# K60_2014_12_12.net
KiCad netlist of a schematic drawn in Altium Designer
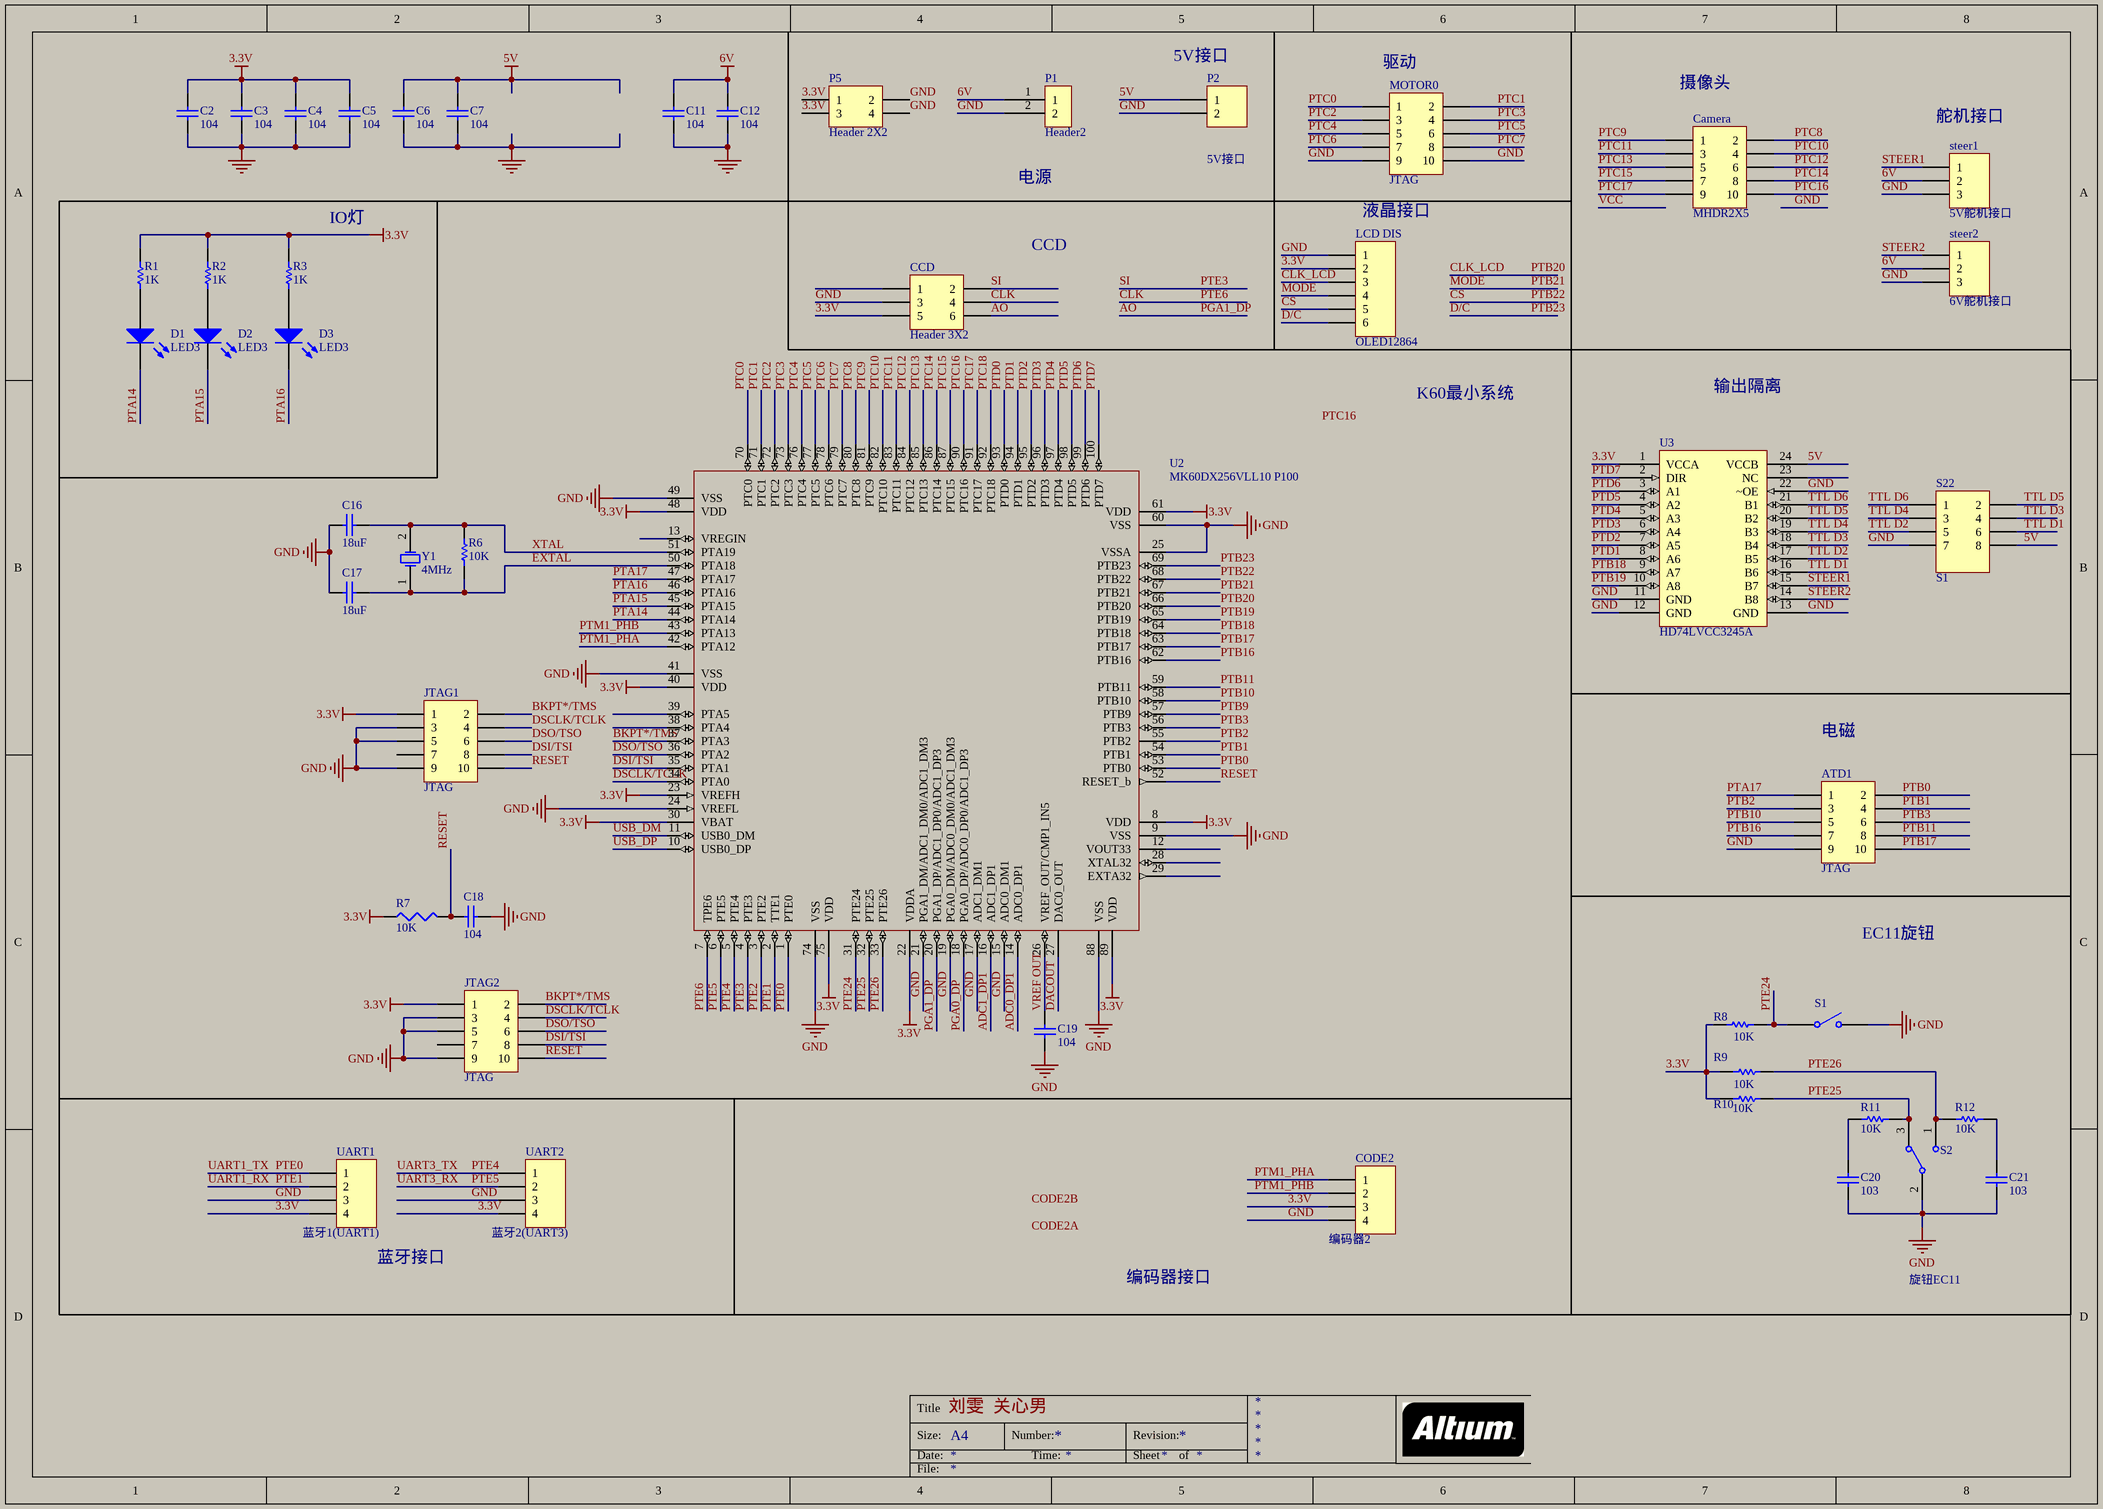
[diagram p0: K60 2014 12 12.SchDoc]

(export (version "E")
  (design (tool "Eeschema 10.0.6"))
  (components
    (comp (ref "ATD1")
      (value "JTAG")
      (footprint "K60 2014 12 12:IDC10S")
      (description "Header, 5-Pin, Dual row")
      (fields (field (name "PUBLISHER") "Altium Limited"))
      (libsource (lib "北京工商大学智能车 K60 摄像头") (part "MHDR2X5"))
    )
    (comp (ref "C2")
      (value "104")
      (footprint "0603")
      (description "Capacitor")
      (libsource (lib "电阻电容") (part "Cap 0603"))
    )
    (comp (ref "C3")
      (value "104")
      (footprint "0603")
      (description "Capacitor")
      (libsource (lib "电阻电容") (part "Cap 0603"))
    )
    (comp (ref "C4")
      (value "104")
      (footprint "0603")
      (description "Capacitor")
      (libsource (lib "电阻电容") (part "Cap 0603"))
    )
    (comp (ref "C5")
      (value "104")
      (footprint "0603")
      (description "Capacitor")
      (libsource (lib "电阻电容") (part "Cap 0603"))
    )
    (comp (ref "C6")
      (value "104")
      (footprint "0603")
      (description "Capacitor")
      (libsource (lib "电阻电容") (part "Cap 0603"))
    )
    (comp (ref "C7")
      (value "104")
      (footprint "0603")
      (description "Capacitor")
      (libsource (lib "电阻电容") (part "Cap 0603"))
    )
    (comp (ref "C11")
      (value "104")
      (footprint "0603")
      (description "Capacitor")
      (libsource (lib "电阻电容") (part "Cap 0603"))
    )
    (comp (ref "C12")
      (value "104")
      (footprint "0603")
      (description "Capacitor")
      (libsource (lib "电阻电容") (part "Cap 0603"))
    )
    (comp (ref "C16")
      (value "18uF")
      (footprint "0603")
      (description "Capacitor")
      (libsource (lib "电阻电容") (part "Cap 0603"))
    )
    (comp (ref "C17")
      (value "18uF")
      (footprint "0603")
      (description "Capacitor")
      (libsource (lib "电阻电容") (part "Cap 0603"))
    )
    (comp (ref "C18")
      (value "104")
      (footprint "0603")
      (description "Capacitor (Semiconductor SIM Model)")
      (fields (field (name "Comment") "C1") (field (name "PUBLISHER") "Altium Limited"))
      (libsource (lib "北京工商大学智能车 K60 摄像头") (part "Cap Semi"))
    )
    (comp (ref "C19")
      (value "104")
      (footprint "0603")
      (description "Capacitor (Semiconductor SIM Model)")
      (fields (field (name "Comment") "C1") (field (name "PUBLISHER") "Altium Limited"))
      (libsource (lib "北京工商大学智能车 K60 摄像头") (part "Cap Semi"))
    )
    (comp (ref "C20")
      (value "103")
      (footprint "0603")
      (description "Capacitor")
      (libsource (lib "电阻电容") (part "Cap 0603"))
    )
    (comp (ref "C21")
      (value "103")
      (footprint "0603")
      (description "Capacitor")
      (libsource (lib "电阻电容") (part "Cap 0603"))
    )
    (comp (ref "Camera")
      (value "MHDR2X5")
      (footprint "IDC10S")
      (description "Header, 5-Pin, Dual row")
      (fields (field (name "PUBLISHER") "Altium Limited"))
      (libsource (lib "Miscellaneous Connectors") (part "MHDR2X5"))
    )
    (comp (ref "CCD")
      (value "Header 3X2")
      (footprint "HDR2X3")
      (description "Header, 3-Pin, Dual row")
      (fields (field (name "PUBLISHER") "Altium Limited"))
      (libsource (lib "Miscellaneous Connectors") (part "Header 3X2"))
    )
    (comp (ref "CODE2")
      (value "编码器2")
      (footprint "HDR1X4")
      (description "Header, 4-Pin")
      (fields (field (name "PUBLISHER") "Altium Limited"))
      (libsource (lib "K60 2014 12 12") (part "Header 4"))
    )
    (comp (ref "D1")
      (value "LED3")
      (footprint "0805")
      (description "Typical BLUE SiC LED")
      (fields (field (name "PUBLISHER") "Altium Limited"))
      (libsource (lib "北京工商大学智能车 K60 摄像头") (part "LED3"))
    )
    (comp (ref "D2")
      (value "LED3")
      (footprint "0805")
      (description "Typical BLUE SiC LED")
      (fields (field (name "PUBLISHER") "Altium Limited"))
      (libsource (lib "北京工商大学智能车 K60 摄像头") (part "LED3"))
    )
    (comp (ref "D3")
      (value "LED3")
      (footprint "0805")
      (description "Typical BLUE SiC LED")
      (fields (field (name "PUBLISHER") "Altium Limited"))
      (libsource (lib "北京工商大学智能车 K60 摄像头") (part "LED3"))
    )
    (comp (ref "JTAG1")
      (value "JTAG")
      (footprint "接口1:JTAG-2.0")
      (description "Header, 5-Pin, Dual row")
      (fields (field (name "PUBLISHER") "Altium Limited"))
      (libsource (lib "北京工商大学智能车 K60 摄像头") (part "MHDR2X5"))
    )
    (comp (ref "JTAG2")
      (value "JTAG")
      (footprint "2014 10 1 主控板 KL25Z128VLK42:MHDR2X5")
      (description "Header, 5-Pin, Dual row")
      (fields (field (name "PUBLISHER") "Altium Limited"))
      (libsource (lib "北京工商大学智能车 K60 摄像头") (part "MHDR2X5"))
    )
    (comp (ref "LCD DIS")
      (value "OLED12864")
      (footprint "HDR1X6")
      (description "Header, 6-Pin")
      (fields (field (name "PUBLISHER") "Altium Limited"))
      (libsource (lib "Miscellaneous Connectors") (part "Header 6"))
    )
    (comp (ref "MOTOR0")
      (value "JTAG")
      (footprint "K60 2014 12 12:IDC10S")
      (description "Header, 5-Pin, Dual row")
      (fields (field (name "PUBLISHER") "Altium Limited"))
      (libsource (lib "北京工商大学智能车 K60 摄像头") (part "MHDR2X5"))
    )
    (comp (ref "P1") (value "Header2") (footprint "DIP2-2.54") (libsource (lib "接口1") (part "Header2")))
    (comp (ref "P2")
      (value "5V接口")
      (footprint "HDR1X2")
      (description "Header, 2-Pin")
      (fields (field (name "PUBLISHER") "Altium Limited"))
      (libsource (lib "Miscellaneous Connectors") (part "Header 2"))
    )
    (comp (ref "P5")
      (value "Header 2X2")
      (footprint "HDR2X2")
      (description "Header, 2-Pin, Dual row")
      (fields (field (name "PUBLISHER") "Altium Limited"))
      (libsource (lib "Miscellaneous Connectors") (part "Header 2X2"))
    )
    (comp (ref "R1")
      (value "1K")
      (footprint "0603")
      (description "Resistor")
      (libsource (lib "电阻电容") (part "Res0603"))
    )
    (comp (ref "R2")
      (value "1K")
      (footprint "0603")
      (description "Resistor")
      (libsource (lib "电阻电容") (part "Res0603"))
    )
    (comp (ref "R3")
      (value "1K")
      (footprint "0603")
      (description "Resistor")
      (libsource (lib "电阻电容") (part "Res0603"))
    )
    (comp (ref "R6")
      (value "10K")
      (footprint "0603")
      (description "Resistor")
      (libsource (lib "电阻电容") (part "Res0603"))
    )
    (comp (ref "R7")
      (value "10K")
      (footprint "0603")
      (description "Resistor")
      (fields (field (name "Comment") "Res3") (field (name "PUBLISHER") "Altium Limited"))
      (libsource (lib "北京工商大学智能车 K60 摄像头") (part "Res3"))
    )
    (comp (ref "R8")
      (value "10K")
      (footprint "0603")
      (description "Resistor")
      (libsource (lib "电阻电容") (part "Res0603"))
    )
    (comp (ref "R9")
      (value "10K")
      (footprint "0603")
      (description "Resistor")
      (libsource (lib "电阻电容") (part "Res0603"))
    )
    (comp (ref "R10")
      (value "10K")
      (footprint "0603")
      (description "Resistor")
      (libsource (lib "电阻电容") (part "Res0603"))
    )
    (comp (ref "R11")
      (value "10K")
      (footprint "0603")
      (description "Resistor")
      (libsource (lib "电阻电容") (part "Res0603"))
    )
    (comp (ref "R12")
      (value "10K")
      (footprint "0603")
      (description "Resistor")
      (libsource (lib "电阻电容") (part "Res0603"))
    )
    (comp (ref "S1")
      (value "~")
      (footprint "BTBU CAR 摄像 K60 2013 4 20:Code_Switch")
      (description "Single-Pole, Single-Throw Switch")
      (fields (field (name "PUBLISHER") "Altium Limited"))
      (libsource (lib "北京工商大学智能车 K60 摄像头") (part "SW-SPST"))
    )
    (comp (ref "S2")
      (value "~")
      (footprint "BTBU CAR 摄像 K60 2013 4 20:Code_Switch")
      (description "SPDT Subminiature Toggle Switch, Right Angle Mounting, Vertical Actuation")
      (fields (field (name "PUBLISHER") "Altium Limited"))
      (libsource (lib "Miscellaneous Devices") (part "SW-SPDT"))
    )
    (comp (ref "S22")
      (value "S1")
      (footprint "K60 2014 12 12:IDC10S")
      (description "Header, 5-Pin, Dual row")
      (fields (field (name "PUBLISHER") "Altium Limited"))
      (libsource (lib "") (part "MHDR2X5_1"))
    )
    (comp (ref "steer1")
      (value "5V舵机接口")
      (footprint "HDR1X3")
      (description "Header, 3-Pin")
      (fields (field (name "PUBLISHER") "Altium Limited"))
      (libsource (lib "Miscellaneous Connectors") (part "Header 3"))
    )
    (comp (ref "steer2")
      (value "6V舵机接口")
      (footprint "HDR1X3")
      (description "Header, 3-Pin")
      (fields (field (name "PUBLISHER") "Altium Limited"))
      (libsource (lib "Miscellaneous Connectors") (part "Header 3"))
    )
    (comp (ref "U2")
      (value "MK60DX256VLL10 P100")
      (footprint "BTBU CAR 摄像 K60 2013 4 20:983-01_M")
      (description "Low Cost Integrated Multiprotocol Processor")
      (fields (field (name "PUBLISHER") "Altium Limited"))
      (libsource (lib "2012 6 10 智能车 摄像头组") (part "MC68LC302PU16"))
    )
    (comp (ref "U3")
      (value "HD74LVCC3245A")
      (footprint "HD74LVCC3245A")
      (description "Octal Bus Transceiver with adjustable output voltage  and 3-state Outputs")
      (libsource (lib "Voltage IC") (part "HD74LVCC3245A"))
    )
    (comp (ref "UART1")
      (value "蓝牙1(UART1)")
      (footprint "HDR1X4")
      (description "Header, 4-Pin")
      (fields (field (name "PUBLISHER") "Altium Limited"))
      (libsource (lib "Miscellaneous Connectors") (part "Header 4"))
    )
    (comp (ref "UART2")
      (value "蓝牙2(UART3)")
      (footprint "HDR1X4")
      (description "Header, 4-Pin")
      (fields (field (name "PUBLISHER") "Altium Limited"))
      (libsource (lib "Miscellaneous Connectors") (part "Header 4"))
    )
    (comp (ref "Y1")
      (value "4MHz")
      (footprint "晶振11.2-4.7-3.6")
      (description "Crystal Oscillator")
      (fields (field (name "PUBLISHER") "Altium Limited"))
      (libsource (lib "北京工商大学智能车 K60 摄像头") (part "XTAL"))
    )
  )
  (nets
    (net (code "1") (name "/ADC0_DP1") (class "Default")
      (node (ref "U2") (pin "14") (pinfunction "ADC0_DP1_14") (pintype "bidirectional"))
    )
    (net (code "2") (name "/ADC1_DP1") (class "Default")
      (node (ref "U2") (pin "16") (pinfunction "ADC1_DP1_16") (pintype "bidirectional"))
    )
    (net (code "3") (name "/AO") (class "Default")
      (node (ref "CCD") (pin "6") (pinfunction "6_6") (pintype "passive"))
      (node (ref "U2") (pin "20") (pinfunction "PGA1_DP/ADC1_DP0/ADC1_DP3_20") (pintype "bidirectional"))
    )
    (net (code "4") (name "/BKPT*{slash}TMS") (class "Default")
      (node (ref "JTAG1") (pin "2") (pinfunction "2_2") (pintype "passive"))
      (node (ref "JTAG2") (pin "2") (pinfunction "2_2") (pintype "passive"))
      (node (ref "U2") (pin "37") (pinfunction "PTA3_37") (pintype "bidirectional"))
    )
    (net (code "5") (name "/CLK") (class "Default")
      (node (ref "CCD") (pin "4") (pinfunction "4_4") (pintype "passive"))
      (node (ref "U2") (pin "7") (pinfunction "TPE6_7") (pintype "bidirectional"))
    )
    (net (code "6") (name "/CLK_LCD") (class "Default")
      (node (ref "LCD DIS") (pin "3") (pinfunction "3_3") (pintype "passive"))
      (node (ref "U2") (pin "66") (pinfunction "PTB20_66") (pintype "bidirectional"))
    )
    (net (code "9") (name "/CS") (class "Default")
      (node (ref "LCD DIS") (pin "5") (pinfunction "5_5") (pintype "passive"))
      (node (ref "U2") (pin "68") (pinfunction "PTB22_68") (pintype "bidirectional"))
    )
    (net (code "10") (name "/DACOUT") (class "Default")
      (node (ref "U2") (pin "27") (pinfunction "DAC0_OUT_27") (pintype "passive"))
    )
    (net (code "11") (name "/DSCLK{slash}TCLK") (class "Default")
      (node (ref "JTAG1") (pin "4") (pinfunction "4_4") (pintype "passive"))
      (node (ref "JTAG2") (pin "4") (pinfunction "4_4") (pintype "passive"))
      (node (ref "U2") (pin "34") (pinfunction "PTA0_34") (pintype "bidirectional"))
    )
    (net (code "12") (name "/DSI{slash}TSI") (class "Default")
      (node (ref "JTAG1") (pin "8") (pinfunction "8_8") (pintype "passive"))
      (node (ref "JTAG2") (pin "8") (pinfunction "8_8") (pintype "passive"))
      (node (ref "U2") (pin "35") (pinfunction "PTA1_35") (pintype "bidirectional"))
    )
    (net (code "13") (name "/DSO{slash}TSO") (class "Default")
      (node (ref "JTAG1") (pin "6") (pinfunction "6_6") (pintype "passive"))
      (node (ref "JTAG2") (pin "6") (pinfunction "6_6") (pintype "passive"))
      (node (ref "U2") (pin "36") (pinfunction "PTA2_36") (pintype "bidirectional"))
    )
    (net (code "14") (name "/D{slash}C") (class "Default")
      (node (ref "LCD DIS") (pin "6") (pinfunction "6_6") (pintype "passive"))
      (node (ref "U2") (pin "69") (pinfunction "PTB23_69") (pintype "bidirectional"))
    )
    (net (code "15") (name "/EXTAL") (class "Default")
      (node (ref "C17") (pin "1") (pinfunction "1_1") (pintype "passive"))
      (node (ref "R6") (pin "1") (pinfunction "1_1") (pintype "passive"))
      (node (ref "U2") (pin "50") (pinfunction "PTA18_50") (pintype "bidirectional"))
      (node (ref "Y1") (pin "1") (pinfunction "OSC1_1") (pintype "passive"))
    )
    (net (code "16") (name "/MODE") (class "Default")
      (node (ref "LCD DIS") (pin "4") (pinfunction "4_4") (pintype "passive"))
      (node (ref "U2") (pin "67") (pinfunction "PTB21_67") (pintype "bidirectional"))
    )
    (net (code "17") (name "/PGA0_DP") (class "Default")
      (node (ref "U2") (pin "18") (pinfunction "PGA0_DP/ADC0_DP0/ADC1_DP3_18") (pintype "bidirectional"))
    )
    (net (code "18") (name "/PTA14") (class "Default")
      (node (ref "D1") (pin "2") (pinfunction "K_2") (pintype "passive"))
      (node (ref "U2") (pin "44") (pinfunction "PTA14_44") (pintype "bidirectional"))
    )
    (net (code "19") (name "/PTA15") (class "Default")
      (node (ref "D2") (pin "2") (pinfunction "K_2") (pintype "passive"))
      (node (ref "U2") (pin "45") (pinfunction "PTA15_45") (pintype "bidirectional"))
    )
    (net (code "20") (name "/PTA16") (class "Default")
      (node (ref "D3") (pin "2") (pinfunction "K_2") (pintype "passive"))
      (node (ref "U2") (pin "46") (pinfunction "PTA16_46") (pintype "bidirectional"))
    )
    (net (code "21") (name "/PTA17") (class "Default")
      (node (ref "ATD1") (pin "1") (pinfunction "1_1") (pintype "passive"))
      (node (ref "U2") (pin "47") (pinfunction "PTA17_47") (pintype "bidirectional"))
    )
    (net (code "22") (name "/PTB0") (class "Default")
      (node (ref "ATD1") (pin "2") (pinfunction "2_2") (pintype "passive"))
      (node (ref "U2") (pin "53") (pinfunction "PTB0_53") (pintype "bidirectional"))
    )
    (net (code "23") (name "/PTB1") (class "Default")
      (node (ref "ATD1") (pin "4") (pinfunction "4_4") (pintype "passive"))
      (node (ref "U2") (pin "54") (pinfunction "PTB1_54") (pintype "bidirectional"))
    )
    (net (code "24") (name "/PTB2") (class "Default")
      (node (ref "ATD1") (pin "3") (pinfunction "3_3") (pintype "passive"))
      (node (ref "U2") (pin "55") (pinfunction "PTB2_55") (pintype "power_in"))
    )
    (net (code "25") (name "/PTB3") (class "Default")
      (node (ref "ATD1") (pin "6") (pinfunction "6_6") (pintype "passive"))
      (node (ref "U2") (pin "56") (pinfunction "PTB3_56") (pintype "bidirectional"))
    )
    (net (code "26") (name "/PTB9") (class "Default")
      (node (ref "U2") (pin "57") (pinfunction "PTB9_57") (pintype "bidirectional"))
    )
    (net (code "27") (name "/PTB10") (class "Default")
      (node (ref "ATD1") (pin "5") (pinfunction "5_5") (pintype "passive"))
      (node (ref "U2") (pin "58") (pinfunction "PTB10_58") (pintype "bidirectional"))
    )
    (net (code "28") (name "/PTB11") (class "Default")
      (node (ref "ATD1") (pin "8") (pinfunction "8_8") (pintype "passive"))
      (node (ref "U2") (pin "59") (pinfunction "PTB11_59") (pintype "bidirectional"))
    )
    (net (code "29") (name "/PTB16") (class "Default")
      (node (ref "ATD1") (pin "7") (pinfunction "7_7") (pintype "passive"))
      (node (ref "U2") (pin "62") (pinfunction "PTB16_62") (pintype "bidirectional"))
    )
    (net (code "30") (name "/PTB17") (class "Default")
      (node (ref "ATD1") (pin "10") (pinfunction "10_10") (pintype "passive"))
      (node (ref "U2") (pin "63") (pinfunction "PTB17_63") (pintype "bidirectional"))
    )
    (net (code "31") (name "/PTB18") (class "Default")
      (node (ref "U2") (pin "64") (pinfunction "PTB18_64") (pintype "bidirectional"))
      (node (ref "U3") (pin "9") (pinfunction "A7_9") (pintype "bidirectional"))
    )
    (net (code "32") (name "/PTB19") (class "Default")
      (node (ref "U2") (pin "65") (pinfunction "PTB19_65") (pintype "bidirectional"))
      (node (ref "U3") (pin "10") (pinfunction "A8_10") (pintype "bidirectional"))
    )
    (net (code "33") (name "/PTC0") (class "Default")
      (node (ref "MOTOR0") (pin "1") (pinfunction "1_1") (pintype "passive"))
      (node (ref "U2") (pin "70") (pinfunction "PTC0_70") (pintype "bidirectional"))
    )
    (net (code "34") (name "/PTC1") (class "Default")
      (node (ref "MOTOR0") (pin "2") (pinfunction "2_2") (pintype "passive"))
      (node (ref "U2") (pin "71") (pinfunction "PTC1_71") (pintype "bidirectional"))
    )
    (net (code "35") (name "/PTC2") (class "Default")
      (node (ref "MOTOR0") (pin "3") (pinfunction "3_3") (pintype "passive"))
      (node (ref "U2") (pin "72") (pinfunction "PTC2_72") (pintype "bidirectional"))
    )
    (net (code "36") (name "/PTC3") (class "Default")
      (node (ref "MOTOR0") (pin "4") (pinfunction "4_4") (pintype "passive"))
      (node (ref "U2") (pin "73") (pinfunction "PTC3_73") (pintype "bidirectional"))
    )
    (net (code "37") (name "/PTC4") (class "Default")
      (node (ref "MOTOR0") (pin "5") (pinfunction "5_5") (pintype "passive"))
      (node (ref "U2") (pin "76") (pinfunction "PTC4_76") (pintype "bidirectional"))
    )
    (net (code "38") (name "/PTC5") (class "Default")
      (node (ref "MOTOR0") (pin "6") (pinfunction "6_6") (pintype "passive"))
      (node (ref "U2") (pin "77") (pinfunction "PTC5_77") (pintype "bidirectional"))
    )
    (net (code "39") (name "/PTC6") (class "Default")
      (node (ref "MOTOR0") (pin "7") (pinfunction "7_7") (pintype "passive"))
      (node (ref "U2") (pin "78") (pinfunction "PTC6_78") (pintype "bidirectional"))
    )
    (net (code "40") (name "/PTC7") (class "Default")
      (node (ref "MOTOR0") (pin "8") (pinfunction "8_8") (pintype "passive"))
      (node (ref "U2") (pin "79") (pinfunction "PTC7_79") (pintype "bidirectional"))
    )
    (net (code "41") (name "/PTC8") (class "Default")
      (node (ref "Camera") (pin "2") (pinfunction "2_2") (pintype "passive"))
      (node (ref "U2") (pin "80") (pinfunction "PTC8_80") (pintype "bidirectional"))
    )
    (net (code "42") (name "/PTC9") (class "Default")
      (node (ref "Camera") (pin "1") (pinfunction "1_1") (pintype "passive"))
      (node (ref "U2") (pin "81") (pinfunction "PTC9_81") (pintype "bidirectional"))
    )
    (net (code "43") (name "/PTC10") (class "Default")
      (node (ref "Camera") (pin "4") (pinfunction "4_4") (pintype "passive"))
      (node (ref "U2") (pin "82") (pinfunction "PTC10_82") (pintype "bidirectional"))
    )
    (net (code "44") (name "/PTC11") (class "Default")
      (node (ref "Camera") (pin "3") (pinfunction "3_3") (pintype "passive"))
      (node (ref "U2") (pin "83") (pinfunction "PTC11_83") (pintype "bidirectional"))
    )
    (net (code "45") (name "/PTC12") (class "Default")
      (node (ref "Camera") (pin "6") (pinfunction "6_6") (pintype "passive"))
      (node (ref "U2") (pin "84") (pinfunction "PTC12_84") (pintype "bidirectional"))
    )
    (net (code "46") (name "/PTC13") (class "Default")
      (node (ref "Camera") (pin "5") (pinfunction "5_5") (pintype "passive"))
      (node (ref "U2") (pin "85") (pinfunction "PTC13_85") (pintype "bidirectional"))
    )
    (net (code "47") (name "/PTC14") (class "Default")
      (node (ref "Camera") (pin "8") (pinfunction "8_8") (pintype "passive"))
      (node (ref "U2") (pin "86") (pinfunction "PTC14_86") (pintype "bidirectional"))
    )
    (net (code "48") (name "/PTC15") (class "Default")
      (node (ref "Camera") (pin "7") (pinfunction "7_7") (pintype "passive"))
      (node (ref "U2") (pin "87") (pinfunction "PTC15_87") (pintype "bidirectional"))
    )
    (net (code "49") (name "/PTC16") (class "Default")
      (node (ref "Camera") (pin "10") (pinfunction "10_10") (pintype "passive"))
      (node (ref "U2") (pin "90") (pinfunction "PTC16_90") (pintype "bidirectional"))
    )
    (net (code "50") (name "/PTC17") (class "Default")
      (node (ref "Camera") (pin "9") (pinfunction "9_9") (pintype "passive"))
      (node (ref "U2") (pin "91") (pinfunction "PTC17_91") (pintype "bidirectional"))
    )
    (net (code "51") (name "/PTC18") (class "Default")
      (node (ref "U2") (pin "92") (pinfunction "PTC18_92") (pintype "bidirectional"))
    )
    (net (code "52") (name "/PTD0") (class "Default")
      (node (ref "U2") (pin "93") (pinfunction "PTD0_93") (pintype "bidirectional"))
    )
    (net (code "53") (name "/PTD1") (class "Default")
      (node (ref "U2") (pin "94") (pinfunction "PTD1_94") (pintype "bidirectional"))
      (node (ref "U3") (pin "8") (pinfunction "A6_8") (pintype "bidirectional"))
    )
    (net (code "54") (name "/PTD2") (class "Default")
      (node (ref "U2") (pin "95") (pinfunction "PTD2_95") (pintype "bidirectional"))
      (node (ref "U3") (pin "7") (pinfunction "A5_7") (pintype "bidirectional"))
    )
    (net (code "55") (name "/PTD3") (class "Default")
      (node (ref "U2") (pin "96") (pinfunction "PTD3_96") (pintype "bidirectional"))
      (node (ref "U3") (pin "6") (pinfunction "A4_6") (pintype "bidirectional"))
    )
    (net (code "56") (name "/PTD4") (class "Default")
      (node (ref "U2") (pin "97") (pinfunction "PTD4_97") (pintype "bidirectional"))
      (node (ref "U3") (pin "5") (pinfunction "A3_5") (pintype "bidirectional"))
    )
    (net (code "57") (name "/PTD5") (class "Default")
      (node (ref "U2") (pin "98") (pinfunction "PTD5_98") (pintype "bidirectional"))
      (node (ref "U3") (pin "4") (pinfunction "A2_4") (pintype "bidirectional"))
    )
    (net (code "58") (name "/PTD6") (class "Default")
      (node (ref "U2") (pin "99") (pinfunction "PTD6_99") (pintype "bidirectional"))
      (node (ref "U3") (pin "3") (pinfunction "A1_3") (pintype "bidirectional"))
    )
    (net (code "59") (name "/PTD7") (class "Default")
      (node (ref "U2") (pin "100") (pinfunction "PTD7_100") (pintype "bidirectional"))
      (node (ref "U3") (pin "2") (pinfunction "DIR_2") (pintype "input"))
    )
    (net (code "60") (name "/PTE0") (class "Default")
      (node (ref "U2") (pin "1") (pinfunction "PTE0_1") (pintype "bidirectional"))
      (node (ref "UART1") (pin "1") (pinfunction "1_1") (pintype "passive"))
    )
    (net (code "61") (name "/PTE1") (class "Default")
      (node (ref "U2") (pin "2") (pinfunction "TTE1_2") (pintype "bidirectional"))
      (node (ref "UART1") (pin "2") (pinfunction "2_2") (pintype "passive"))
    )
    (net (code "62") (name "/PTE2") (class "Default")
      (node (ref "U2") (pin "3") (pinfunction "PTE2_3") (pintype "bidirectional"))
    )
    (net (code "63") (name "/PTE3") (class "Default")
      (node (ref "CCD") (pin "2") (pinfunction "2_2") (pintype "passive"))
      (node (ref "U2") (pin "4") (pinfunction "PTE3_4") (pintype "bidirectional"))
    )
    (net (code "64") (name "/PTE4") (class "Default")
      (node (ref "U2") (pin "5") (pinfunction "PTE4_5") (pintype "bidirectional"))
      (node (ref "UART2") (pin "1") (pinfunction "1_1") (pintype "passive"))
    )
    (net (code "65") (name "/PTE5") (class "Default")
      (node (ref "U2") (pin "6") (pinfunction "PTE5_6") (pintype "bidirectional"))
      (node (ref "UART2") (pin "2") (pinfunction "2_2") (pintype "passive"))
    )
    (net (code "66") (name "/PTE24") (class "Default")
      (node (ref "R8") (pin "2") (pinfunction "2_2") (pintype "passive"))
      (node (ref "S1") (pin "1") (pinfunction "COMMON_1") (pintype "passive"))
      (node (ref "U2") (pin "31") (pinfunction "PTE24_31") (pintype "bidirectional"))
    )
    (net (code "67") (name "/PTE25") (class "Default")
      (node (ref "R10") (pin "2") (pinfunction "2_2") (pintype "passive"))
      (node (ref "R11") (pin "2") (pinfunction "2_2") (pintype "passive"))
      (node (ref "S2") (pin "3") (pinfunction "3_3") (pintype "passive"))
      (node (ref "U2") (pin "32") (pinfunction "PTE25_32") (pintype "bidirectional"))
    )
    (net (code "68") (name "/PTE26") (class "Default")
      (node (ref "R12") (pin "1") (pinfunction "1_1") (pintype "passive"))
      (node (ref "R9") (pin "2") (pinfunction "2_2") (pintype "passive"))
      (node (ref "S2") (pin "1") (pinfunction "1_1") (pintype "passive"))
      (node (ref "U2") (pin "33") (pinfunction "PTE26_33") (pintype "bidirectional"))
    )
    (net (code "69") (name "/PTM1_PHA") (class "Default")
      (node (ref "CODE2") (pin "1") (pinfunction "1_1") (pintype "passive"))
      (node (ref "U2") (pin "42") (pinfunction "PTA12_42") (pintype "bidirectional"))
    )
    (net (code "70") (name "/PTM1_PHB") (class "Default")
      (node (ref "CODE2") (pin "2") (pinfunction "2_2") (pintype "passive"))
      (node (ref "U2") (pin "43") (pinfunction "PTA13_43") (pintype "bidirectional"))
    )
    (net (code "71") (name "/RESET") (class "Default")
      (node (ref "C18") (pin "1") (pinfunction "1_1") (pintype "passive"))
      (node (ref "JTAG1") (pin "10") (pinfunction "10_10") (pintype "passive"))
      (node (ref "JTAG2") (pin "10") (pinfunction "10_10") (pintype "passive"))
      (node (ref "R7") (pin "2") (pinfunction "2_2") (pintype "passive"))
      (node (ref "U2") (pin "52") (pinfunction "RESET_b_52") (pintype "output"))
    )
    (net (code "72") (name "/STEER1") (class "Default")
      (node (ref "U3") (pin "15") (pinfunction "B7_15") (pintype "bidirectional"))
      (node (ref "steer1") (pin "1") (pinfunction "1_1") (pintype "passive"))
    )
    (net (code "73") (name "/STEER2") (class "Default")
      (node (ref "U3") (pin "14") (pinfunction "B8_14") (pintype "bidirectional"))
      (node (ref "steer2") (pin "1") (pinfunction "1_1") (pintype "passive"))
    )
    (net (code "74") (name "/TTL D1") (class "Default")
      (node (ref "S22") (pin "6") (pinfunction "6_6") (pintype "passive"))
      (node (ref "U3") (pin "16") (pinfunction "B6_16") (pintype "bidirectional"))
    )
    (net (code "75") (name "/TTL D2") (class "Default")
      (node (ref "S22") (pin "5") (pinfunction "5_5") (pintype "passive"))
      (node (ref "U3") (pin "17") (pinfunction "B5_17") (pintype "bidirectional"))
    )
    (net (code "76") (name "/TTL D3") (class "Default")
      (node (ref "S22") (pin "4") (pinfunction "4_4") (pintype "passive"))
      (node (ref "U3") (pin "18") (pinfunction "B4_18") (pintype "bidirectional"))
    )
    (net (code "77") (name "/TTL D4") (class "Default")
      (node (ref "S22") (pin "3") (pinfunction "3_3") (pintype "passive"))
      (node (ref "U3") (pin "19") (pinfunction "B3_19") (pintype "bidirectional"))
    )
    (net (code "78") (name "/TTL D5") (class "Default")
      (node (ref "S22") (pin "2") (pinfunction "2_2") (pintype "passive"))
      (node (ref "U3") (pin "20") (pinfunction "B2_20") (pintype "bidirectional"))
    )
    (net (code "79") (name "/TTL D6") (class "Default")
      (node (ref "S22") (pin "1") (pinfunction "1_1") (pintype "passive"))
      (node (ref "U3") (pin "21") (pinfunction "B1_21") (pintype "bidirectional"))
    )
    (net (code "80") (name "/USB_DM") (class "Default")
      (node (ref "U2") (pin "11") (pinfunction "USB0_DM_11") (pintype "bidirectional"))
    )
    (net (code "81") (name "/USB_DP") (class "Default")
      (node (ref "U2") (pin "10") (pinfunction "USB0_DP_10") (pintype "bidirectional"))
    )
    (net (code "83") (name "/VREF OUT") (class "Default")
      (node (ref "C19") (pin "2") (pinfunction "2_2") (pintype "passive"))
      (node (ref "U2") (pin "26") (pinfunction "VREF_OUT/CMP1_IN5_26") (pintype "bidirectional"))
    )
    (net (code "84") (name "/XTAL") (class "Default")
      (node (ref "C16") (pin "1") (pinfunction "1_1") (pintype "passive"))
      (node (ref "R6") (pin "2") (pinfunction "2_2") (pintype "passive"))
      (node (ref "U2") (pin "51") (pinfunction "PTA19_51") (pintype "bidirectional"))
      (node (ref "Y1") (pin "2") (pinfunction "OSC2_2") (pintype "passive"))
    )
    (net (code "85") (name "3.3V") (class "Default")
      (node (ref "C2") (pin "2") (pinfunction "2_2") (pintype "passive"))
      (node (ref "C3") (pin "2") (pinfunction "2_2") (pintype "passive"))
      (node (ref "C4") (pin "2") (pinfunction "2_2") (pintype "passive"))
      (node (ref "C5") (pin "2") (pinfunction "2_2") (pintype "passive"))
      (node (ref "CCD") (pin "5") (pinfunction "5_5") (pintype "passive"))
      (node (ref "CODE2") (pin "3") (pinfunction "3_3") (pintype "passive"))
      (node (ref "JTAG1") (pin "1") (pinfunction "1_1") (pintype "passive"))
      (node (ref "JTAG2") (pin "1") (pinfunction "1_1") (pintype "passive"))
      (node (ref "LCD DIS") (pin "2") (pinfunction "2_2") (pintype "passive"))
      (node (ref "P5") (pin "1") (pinfunction "1_1") (pintype "passive"))
      (node (ref "P5") (pin "3") (pinfunction "3_3") (pintype "passive"))
      (node (ref "R1") (pin "2") (pinfunction "2_2") (pintype "passive"))
      (node (ref "R10") (pin "1") (pinfunction "1_1") (pintype "passive"))
      (node (ref "R2") (pin "2") (pinfunction "2_2") (pintype "passive"))
      (node (ref "R3") (pin "2") (pinfunction "2_2") (pintype "passive"))
      (node (ref "R7") (pin "1") (pinfunction "1_1") (pintype "passive"))
      (node (ref "R8") (pin "1") (pinfunction "1_1") (pintype "passive"))
      (node (ref "R9") (pin "1") (pinfunction "1_1") (pintype "passive"))
      (node (ref "U2") (pin "22") (pinfunction "VDDA_22") (pintype "power_in"))
      (node (ref "U2") (pin "23") (pinfunction "VREFH_23") (pintype "input"))
      (node (ref "U2") (pin "30") (pinfunction "VBAT_30") (pintype "power_in"))
      (node (ref "U2") (pin "40") (pinfunction "VDD_40") (pintype "power_in"))
      (node (ref "U2") (pin "48") (pinfunction "VDD_48") (pintype "power_in"))
      (node (ref "U2") (pin "61") (pinfunction "VDD_61") (pintype "passive"))
      (node (ref "U2") (pin "75") (pinfunction "VDD_75") (pintype "power_in"))
      (node (ref "U2") (pin "8") (pinfunction "VDD_8") (pintype "power_in"))
      (node (ref "U2") (pin "89") (pinfunction "VDD_89") (pintype "power_in"))
      (node (ref "U3") (pin "1") (pinfunction "VCCA_1") (pintype "power_in"))
      (node (ref "UART1") (pin "4") (pinfunction "4_4") (pintype "passive"))
      (node (ref "UART2") (pin "4") (pinfunction "4_4") (pintype "passive"))
    )
    (net (code "86") (name "5V") (class "Default")
      (node (ref "C6") (pin "2") (pinfunction "2_2") (pintype "passive"))
      (node (ref "C7") (pin "2") (pinfunction "2_2") (pintype "passive"))
      (node (ref "P2") (pin "1") (pinfunction "1_1") (pintype "passive"))
      (node (ref "S22") (pin "8") (pinfunction "8_8") (pintype "passive"))
      (node (ref "U3") (pin "24") (pinfunction "VCCB_24") (pintype "power_in"))
    )
    (net (code "87") (name "6V") (class "Default")
      (node (ref "C11") (pin "2") (pinfunction "2_2") (pintype "passive"))
      (node (ref "C12") (pin "2") (pinfunction "2_2") (pintype "passive"))
      (node (ref "P1") (pin "1") (pinfunction "1_1") (pintype "passive"))
      (node (ref "steer1") (pin "2") (pinfunction "2_2") (pintype "passive"))
      (node (ref "steer2") (pin "2") (pinfunction "2_2") (pintype "passive"))
    )
    (net (code "88") (name "GND") (class "Default")
      (node (ref "ATD1") (pin "9") (pinfunction "9_9") (pintype "passive"))
      (node (ref "C11") (pin "1") (pinfunction "1_1") (pintype "passive"))
      (node (ref "C12") (pin "1") (pinfunction "1_1") (pintype "passive"))
      (node (ref "C16") (pin "2") (pinfunction "2_2") (pintype "passive"))
      (node (ref "C17") (pin "2") (pinfunction "2_2") (pintype "passive"))
      (node (ref "C18") (pin "2") (pinfunction "2_2") (pintype "passive"))
      (node (ref "C19") (pin "1") (pinfunction "1_1") (pintype "passive"))
      (node (ref "C2") (pin "1") (pinfunction "1_1") (pintype "passive"))
      (node (ref "C20") (pin "1") (pinfunction "1_1") (pintype "passive"))
      (node (ref "C21") (pin "1") (pinfunction "1_1") (pintype "passive"))
      (node (ref "C3") (pin "1") (pinfunction "1_1") (pintype "passive"))
      (node (ref "C4") (pin "1") (pinfunction "1_1") (pintype "passive"))
      (node (ref "C5") (pin "1") (pinfunction "1_1") (pintype "passive"))
      (node (ref "C6") (pin "1") (pinfunction "1_1") (pintype "passive"))
      (node (ref "C7") (pin "1") (pinfunction "1_1") (pintype "passive"))
      (node (ref "CCD") (pin "3") (pinfunction "3_3") (pintype "passive"))
      (node (ref "CODE2") (pin "4") (pinfunction "4_4") (pintype "passive"))
      (node (ref "JTAG1") (pin "3") (pinfunction "3_3") (pintype "passive"))
      (node (ref "JTAG1") (pin "5") (pinfunction "5_5") (pintype "passive"))
      (node (ref "JTAG1") (pin "9") (pinfunction "9_9") (pintype "passive"))
      (node (ref "JTAG2") (pin "3") (pinfunction "3_3") (pintype "passive"))
      (node (ref "JTAG2") (pin "5") (pinfunction "5_5") (pintype "passive"))
      (node (ref "JTAG2") (pin "9") (pinfunction "9_9") (pintype "passive"))
      (node (ref "LCD DIS") (pin "1") (pinfunction "1_1") (pintype "passive"))
      (node (ref "MOTOR0") (pin "10") (pinfunction "10_10") (pintype "passive"))
      (node (ref "MOTOR0") (pin "9") (pinfunction "9_9") (pintype "passive"))
      (node (ref "P1") (pin "2") (pinfunction "2_2") (pintype "passive"))
      (node (ref "P2") (pin "2") (pinfunction "2_2") (pintype "passive"))
      (node (ref "P5") (pin "2") (pinfunction "2_2") (pintype "passive"))
      (node (ref "P5") (pin "4") (pinfunction "4_4") (pintype "passive"))
      (node (ref "S1") (pin "2") (pinfunction "NO_2") (pintype "passive"))
      (node (ref "S2") (pin "2") (pinfunction "2_2") (pintype "passive"))
      (node (ref "S22") (pin "7") (pinfunction "7_7") (pintype "passive"))
      (node (ref "U2") (pin "15") (pinfunction "ADC0_DM1_15") (pintype "bidirectional"))
      (node (ref "U2") (pin "17") (pinfunction "ADC1_DM1_17") (pintype "bidirectional"))
      (node (ref "U2") (pin "19") (pinfunction "PGA0_DM/ADC0_DM0/ADC1_DM3_19") (pintype "bidirectional"))
      (node (ref "U2") (pin "21") (pinfunction "PGA1_DM/ADC1_DM0/ADC1_DM3_21") (pintype "bidirectional"))
      (node (ref "U2") (pin "24") (pinfunction "VREFL_24") (pintype "input"))
      (node (ref "U2") (pin "25") (pinfunction "VSSA_25") (pintype "power_in"))
      (node (ref "U2") (pin "41") (pinfunction "VSS_41") (pintype "power_in"))
      (node (ref "U2") (pin "49") (pinfunction "VSS_49") (pintype "power_in"))
      (node (ref "U2") (pin "60") (pinfunction "VSS_60") (pintype "power_in"))
      (node (ref "U2") (pin "74") (pinfunction "VSS_74") (pintype "power_in"))
      (node (ref "U2") (pin "88") (pinfunction "VSS_88") (pintype "power_in"))
      (node (ref "U2") (pin "9") (pinfunction "VSS_9") (pintype "power_in"))
      (node (ref "U3") (pin "11") (pinfunction "GND_11") (pintype "power_in"))
      (node (ref "U3") (pin "12") (pinfunction "GND_12") (pintype "power_in"))
      (node (ref "U3") (pin "13") (pinfunction "GND_13") (pintype "power_in"))
      (node (ref "U3") (pin "22") (pinfunction "~OE_22") (pintype "input"))
      (node (ref "UART1") (pin "3") (pinfunction "3_3") (pintype "passive"))
      (node (ref "UART2") (pin "3") (pinfunction "3_3") (pintype "passive"))
      (node (ref "steer1") (pin "3") (pinfunction "3_3") (pintype "passive"))
      (node (ref "steer2") (pin "3") (pinfunction "3_3") (pintype "passive"))
    )
    (net (code "89") (name "Net-(C20-Pad2)") (class "Default")
      (node (ref "C20") (pin "2") (pinfunction "2_2") (pintype "passive"))
      (node (ref "R11") (pin "1") (pinfunction "1_1") (pintype "passive"))
    )
    (net (code "90") (name "Net-(C21-Pad2)") (class "Default")
      (node (ref "C21") (pin "2") (pinfunction "2_2") (pintype "passive"))
      (node (ref "R12") (pin "2") (pinfunction "2_2") (pintype "passive"))
    )
    (net (code "91") (name "Net-(D1-A)") (class "Default")
      (node (ref "D1") (pin "1") (pinfunction "A_1") (pintype "passive"))
      (node (ref "R1") (pin "1") (pinfunction "1_1") (pintype "passive"))
    )
    (net (code "92") (name "Net-(D2-A)") (class "Default")
      (node (ref "D2") (pin "1") (pinfunction "A_1") (pintype "passive"))
      (node (ref "R2") (pin "1") (pinfunction "1_1") (pintype "passive"))
    )
    (net (code "93") (name "Net-(D3-A)") (class "Default")
      (node (ref "D3") (pin "1") (pinfunction "A_1") (pintype "passive"))
      (node (ref "R3") (pin "1") (pinfunction "1_1") (pintype "passive"))
    )
    (net (code "94") (name "unconnected-(CCD-Pad1)") (class "Default")
      (node (ref "CCD") (pin "1") (pinfunction "1_1") (pintype "passive"))
    )
    (net (code "95") (name "unconnected-(JTAG1-Pad7)") (class "Default")
      (node (ref "JTAG1") (pin "7") (pinfunction "7_7") (pintype "passive"))
    )
    (net (code "96") (name "unconnected-(JTAG2-Pad7)") (class "Default")
      (node (ref "JTAG2") (pin "7") (pinfunction "7_7") (pintype "passive"))
    )
    (net (code "97") (name "unconnected-(U2-EXTA32-Pad29)") (class "Default")
      (node (ref "U2") (pin "29") (pinfunction "EXTA32_29") (pintype "output"))
    )
    (net (code "98") (name "unconnected-(U2-PTA4-Pad38)") (class "Default")
      (node (ref "U2") (pin "38") (pinfunction "PTA4_38") (pintype "bidirectional"))
    )
    (net (code "99") (name "unconnected-(U2-PTA5-Pad39)") (class "Default")
      (node (ref "U2") (pin "39") (pinfunction "PTA5_39") (pintype "bidirectional"))
    )
    (net (code "100") (name "unconnected-(U2-VOUT33-Pad12)") (class "Default")
      (node (ref "U2") (pin "12") (pinfunction "VOUT33_12") (pintype "power_in"))
    )
    (net (code "101") (name "unconnected-(U2-VREGIN-Pad13)") (class "Default")
      (node (ref "U2") (pin "13") (pinfunction "VREGIN_13") (pintype "bidirectional"))
    )
    (net (code "102") (name "unconnected-(U2-XTAL32-Pad28)") (class "Default")
      (node (ref "U2") (pin "28") (pinfunction "XTAL32_28") (pintype "bidirectional"))
    )
    (net (code "103") (name "unconnected-(U3-NC-Pad23)") (class "Default")
      (node (ref "U3") (pin "23") (pinfunction "NC_23") (pintype "passive"))
    )
  )
)
